# TPSM82822_2A_Buck_Module.net
KiCad netlist of a schematic drawn in Altium Designer
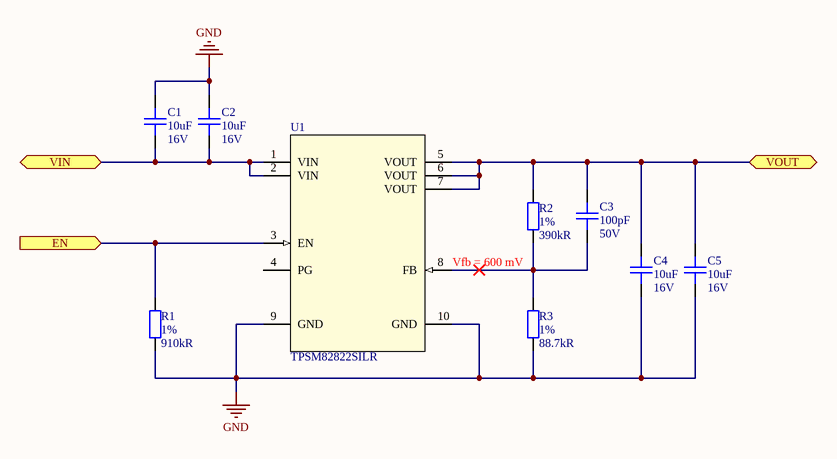
[diagram p0: TPSM82822_2A_Buck_Module.SchDoc]

(export (version "E")
  (design (tool "Eeschema 10.0.6"))
  (components
    (comp (ref "C1")
      (value "CAP CER 10UF 16V X5R 0603")
      (footprint "CAPC1608X08N_0603")
      (description "10µF ±10% 16V Ceramic Capacitor X5R 0603 (1608 Metric)")
      (fields
        (field (name "MANUFACTURER") "Murata")
        (field (name "MANUFACTURER PART NUMBER") "GRM188R61C106KAALJ")
        (field (name "CAPACITANCE") "10uF")
        (field (name "VOLTAGE RATING") "16V")
      )
      (libsource (lib "capacitors_smd") (part "CAP CER 10UF 16V X5R 0603"))
    )
    (comp (ref "C2")
      (value "CAP CER 10UF 16V X5R 0603")
      (footprint "CAPC1608X08N_0603")
      (description "10µF ±10% 16V Ceramic Capacitor X5R 0603 (1608 Metric)")
      (fields
        (field (name "MANUFACTURER") "Murata")
        (field (name "MANUFACTURER PART NUMBER") "GRM188R61C106KAALJ")
        (field (name "CAPACITANCE") "10uF")
        (field (name "VOLTAGE RATING") "16V")
      )
      (libsource (lib "capacitors_smd") (part "CAP CER 10UF 16V X5R 0603"))
    )
    (comp (ref "C3")
      (value "CAP CER 100PF 50V C0G/NPO 0402")
      (footprint "C0402")
      (description "100pF ±5% 50V Ceramic Capacitor C0G, NP0 0402 (1005 Metric)")
      (fields
        (field (name "MANUFACTURER") "Yageo")
        (field (name "MANUFACTURER PART NUMBER") "CC0402JRNPO9BN101")
        (field (name "CAPACITANCE") "100pF")
        (field (name "VOLTAGE") "50V")
      )
      (libsource (lib "capacitors_smd") (part "CAP CER 100PF 50V C0G/NPO 0402"))
    )
    (comp (ref "C4")
      (value "CAP CER 10UF 16V X5R 0603")
      (footprint "CAPC1608X08N_0603")
      (description "10µF ±10% 16V Ceramic Capacitor X5R 0603 (1608 Metric)")
      (fields
        (field (name "MANUFACTURER") "Murata")
        (field (name "MANUFACTURER PART NUMBER") "GRM188R61C106KAALJ")
        (field (name "CAPACITANCE") "10uF")
        (field (name "VOLTAGE RATING") "16V")
      )
      (libsource (lib "capacitors_smd") (part "CAP CER 10UF 16V X5R 0603"))
    )
    (comp (ref "C5")
      (value "CAP CER 10UF 16V X5R 0603")
      (footprint "CAPC1608X08N_0603")
      (description "10µF ±10% 16V Ceramic Capacitor X5R 0603 (1608 Metric)")
      (fields
        (field (name "MANUFACTURER") "Murata")
        (field (name "MANUFACTURER PART NUMBER") "GRM188R61C106KAALJ")
        (field (name "CAPACITANCE") "10uF")
        (field (name "VOLTAGE RATING") "16V")
      )
      (libsource (lib "capacitors_smd") (part "CAP CER 10UF 16V X5R 0603"))
    )
    (comp (ref "R1")
      (value "RES SMD 910K OHM 1% 1/16W 0402")
      (footprint "R_0402")
      (description "910 kOhms ±1% 0.063W, 1/16W Chip Resistor 0402 (1005 Metric) Moisture Resistant Thick Film")
      (fields
        (field (name "MANUFACTURER") "Yageo")
        (field (name "MANUFACTURER PART NUMBER") "RC0402FR-07910KL")
        (field (name "TOLERANCE") "1%")
        (field (name "RESISTANCE") "910kR")
      )
      (libsource (lib "resistors_smd") (part "RES SMD 910K OHM 1% 1/16W 0402"))
    )
    (comp (ref "R2")
      (value "RES SMD 390K OHM 1% 1/16W 0402")
      (footprint "R0402")
      (description "390 kOhms ±1% 0.063W, 1/16W Chip Resistor 0402 (1005 Metric) Moisture Resistant Thick Film")
      (fields
        (field (name "TOLERANCE") "1%")
        (field (name "RESISTANCE") "390kR")
        (field (name "MANUFACTURER") "Yageo")
        (field (name "MANUFACTURER PART NUMBER") "RC0402FR-07390KL")
      )
      (libsource (lib "resistors_smd") (part "RES SMD 390K OHM 1% 1/16W 0402"))
    )
    (comp (ref "R3")
      (value "RES SMD 88.7K OHM 1% 1/16W 0402")
      (footprint "0402R")
      (description "88.7 kOhms ±1% 0.063W, 1/16W Chip Resistor 0402 (1005 Metric) Moisture Resistant Thick Film")
      (fields
        (field (name "TOLERANCE") "1%")
        (field (name "RESISTANCE") "88.7kR")
        (field (name "MANUFACTURER") "Yageo")
        (field (name "MANUFACTURER PART NUMBER") "RC0402FR-0788K7L")
      )
      (libsource (lib "resistors_smd") (part "RES SMD 88.7K OHM 1% 1/16W 0402"))
    )
    (comp (ref "U1")
      (value "TPSM82822SILR")
      (footprint "SIL0010D")
      (description "Non-Isolated PoL Module DC DC Converter 1 Output 0.6 ~ 4V    2A 2.4V - 5.5V Input")
      (fields (field (name "MANUFACTURER") "Texas Instruments"))
      (libsource (lib "dcdc_converters") (part "IC TPSM82822SIL 5.5-V INPUT, 2-A STEP-DOWN MODUL"))
    )
  )
  (nets
    (net (code "1") (name "/EN") (class "Default")
      (node (ref "R1") (pin "1") (pinfunction "1_1") (pintype "passive"))
      (node (ref "U1") (pin "3") (pinfunction "EN_3") (pintype "input"))
    )
    (net (code "2") (name "/VIN") (class "Default")
      (node (ref "C1") (pin "1") (pinfunction "1_1") (pintype "passive"))
      (node (ref "C2") (pin "1") (pinfunction "1_1") (pintype "passive"))
      (node (ref "U1") (pin "1") (pinfunction "VIN_1") (pintype "power_in"))
      (node (ref "U1") (pin "2") (pinfunction "VIN_2") (pintype "power_in"))
    )
    (net (code "3") (name "/VOUT") (class "Default")
      (node (ref "C3") (pin "2") (pinfunction "2_2") (pintype "passive"))
      (node (ref "C4") (pin "1") (pinfunction "1_1") (pintype "passive"))
      (node (ref "C5") (pin "1") (pinfunction "1_1") (pintype "passive"))
      (node (ref "R2") (pin "2") (pinfunction "2_2") (pintype "passive"))
      (node (ref "U1") (pin "5") (pinfunction "VOUT_5") (pintype "power_in"))
      (node (ref "U1") (pin "6") (pinfunction "VOUT_6") (pintype "power_in"))
      (node (ref "U1") (pin "7") (pinfunction "VOUT_7") (pintype "power_in"))
    )
    (net (code "4") (name "GND") (class "Default")
      (node (ref "C1") (pin "2") (pinfunction "2_2") (pintype "passive"))
      (node (ref "C2") (pin "2") (pinfunction "2_2") (pintype "passive"))
      (node (ref "C4") (pin "2") (pinfunction "2_2") (pintype "passive"))
      (node (ref "C5") (pin "2") (pinfunction "2_2") (pintype "passive"))
      (node (ref "R1") (pin "2") (pinfunction "2_2") (pintype "passive"))
      (node (ref "R3") (pin "2") (pinfunction "2_2") (pintype "passive"))
      (node (ref "U1") (pin "10") (pinfunction "GND_10") (pintype "power_in"))
      (node (ref "U1") (pin "9") (pinfunction "GND_9") (pintype "power_in"))
    )
    (net (code "5") (name "Net-(U1-FB)") (class "Default")
      (node (ref "C3") (pin "1") (pinfunction "1_1") (pintype "passive"))
      (node (ref "R2") (pin "1") (pinfunction "1_1") (pintype "passive"))
      (node (ref "R3") (pin "1") (pinfunction "1_1") (pintype "passive"))
      (node (ref "U1") (pin "8") (pinfunction "FB_8") (pintype "input"))
    )
    (net (code "6") (name "unconnected-(U1-PG-Pad4)") (class "Default")
      (node (ref "U1") (pin "4") (pinfunction "PG_4") (pintype "open_collector"))
    )
  )
)
